# BEE_BOARD_TOP.net
KiCad netlist of a schematic drawn in Altium Designer
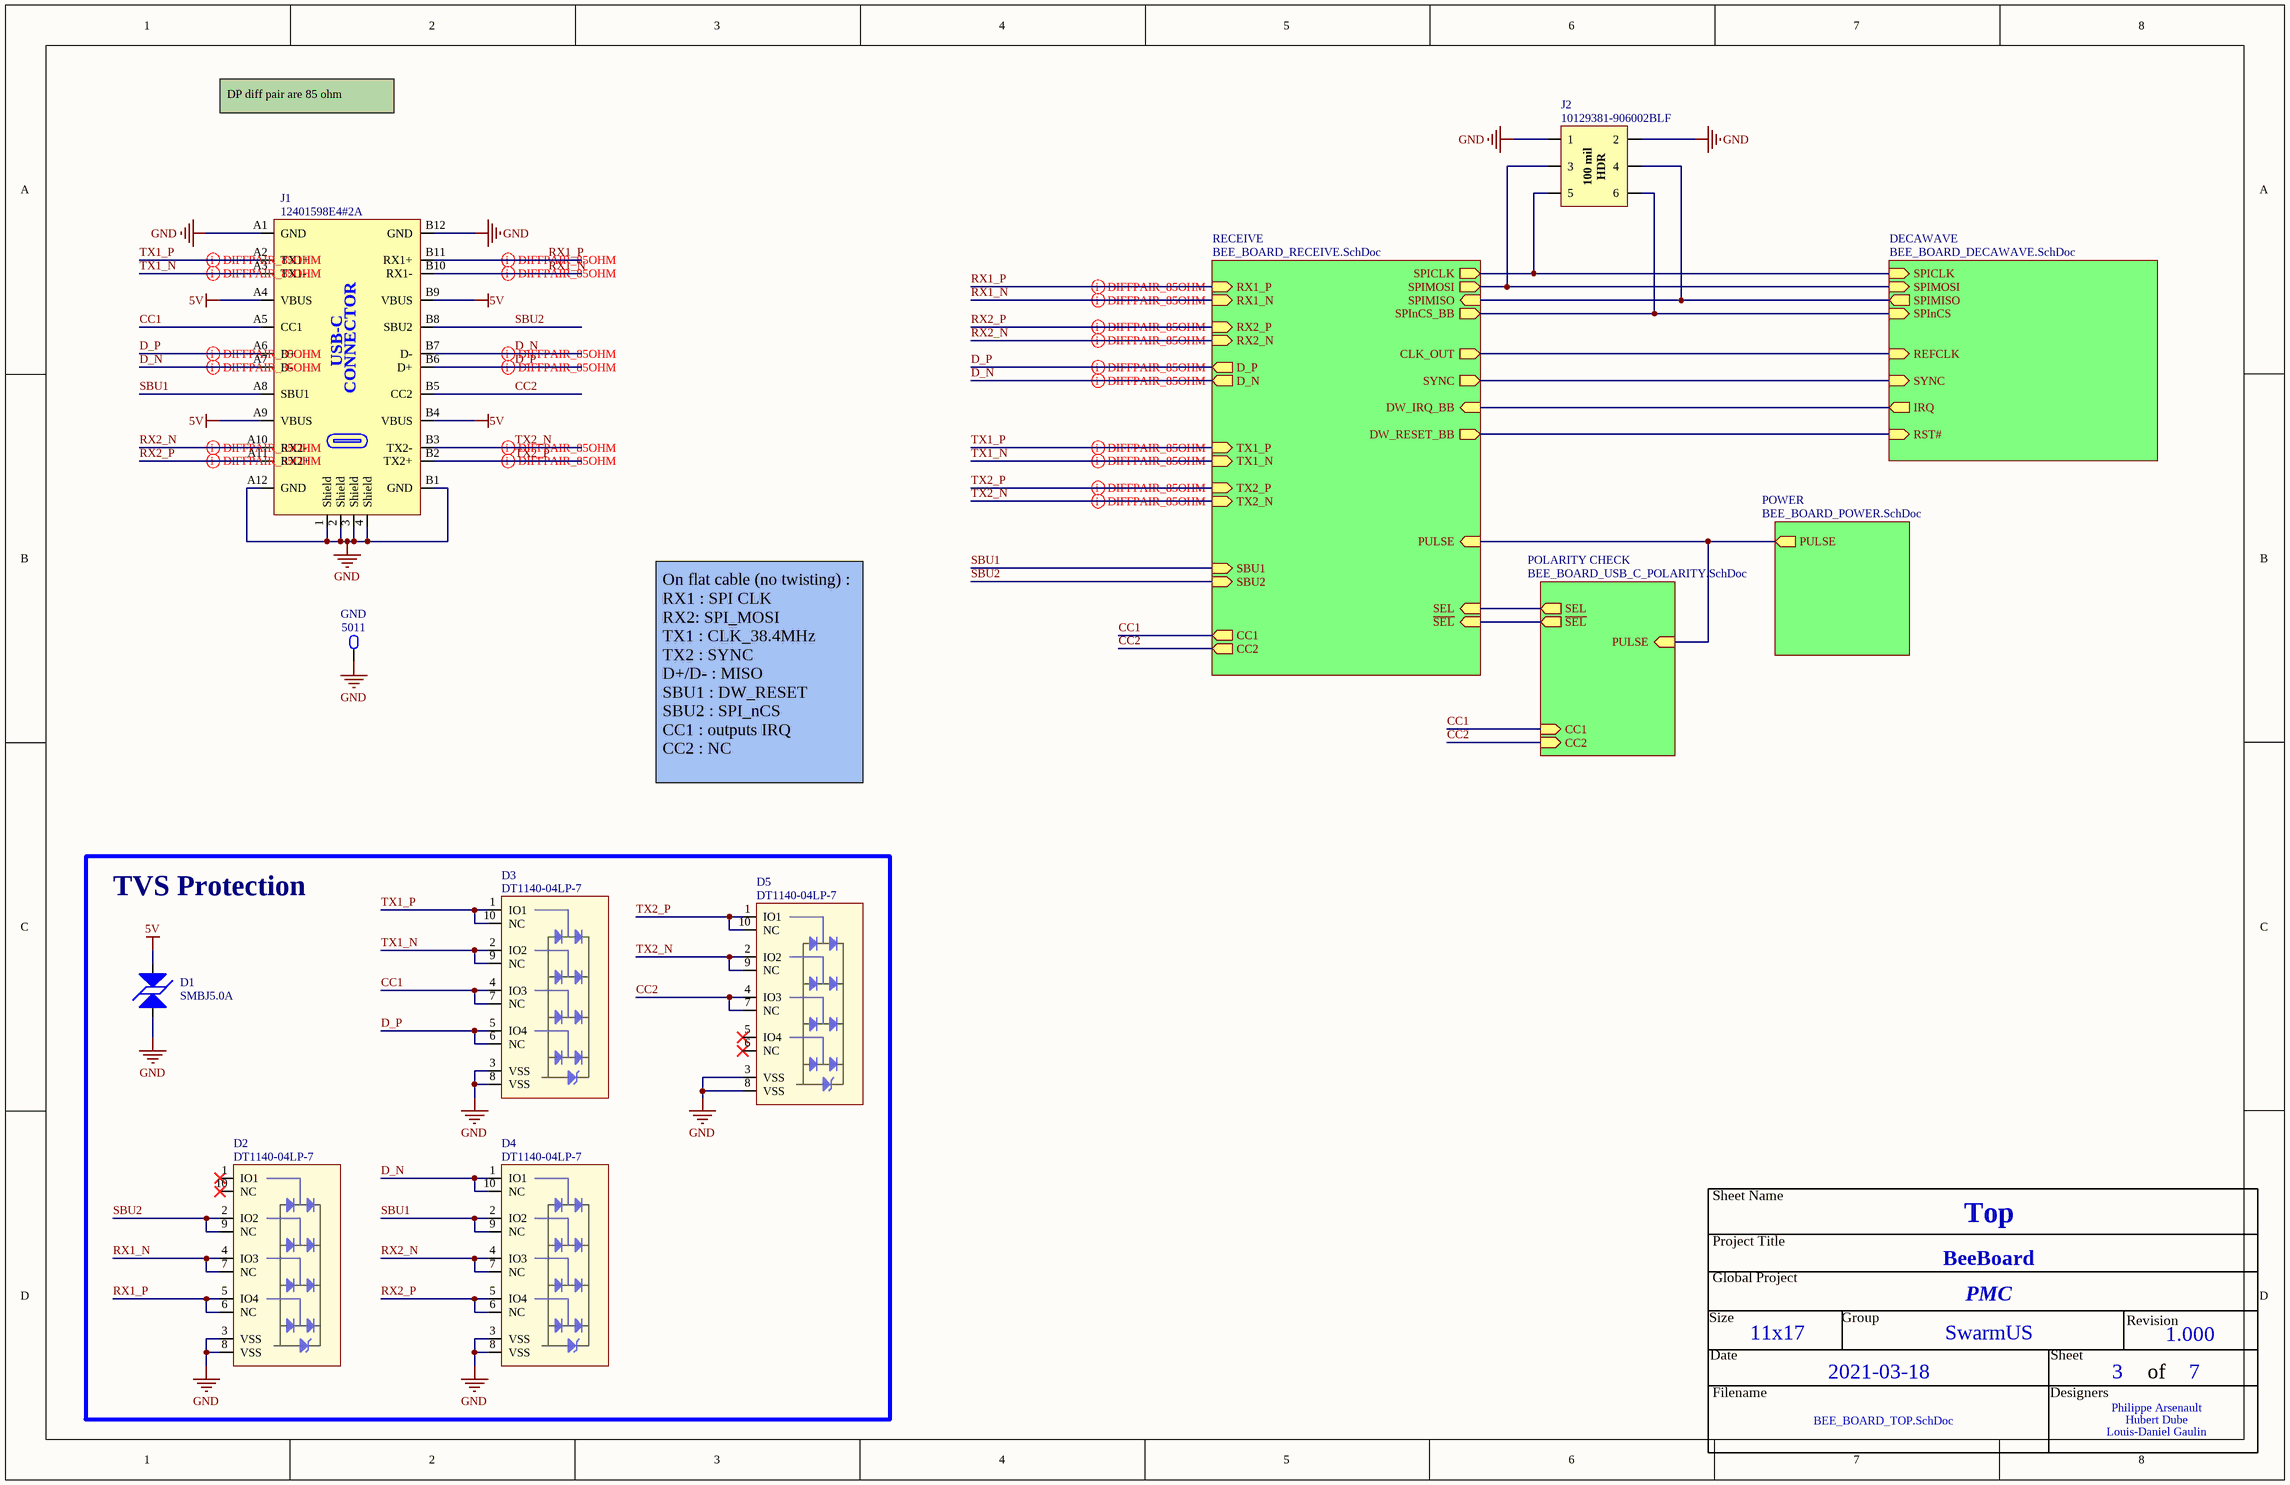
[diagram p0: BEE_BOARD_TOP.SchDoc]

(export (version "E")
  (design (tool "Eeschema 10.0.6"))
  (components
    (comp (ref "D1")
      (value "SMBJ5.0A")
      (footprint "TVS_PWR_SMBJ5.0CA")
      (description "TVS - BIDIR 5V 9.2V 600W - DO214AA")
      (fields
        (field (name "CREATEDBY/DATE") "Louis-Daniel Gaulin / 13-04-2021")
        (field (name "VERIFIEDBY") "Philippe Arsenault/2021-04-14")
      )
      (libsource (lib "SWARMUS_LIB") (part "TVS_PWR_SMBJ5.0A"))
    )
    (comp (ref "D2")
      (value "DT1140-04LP-7")
      (footprint "grams_master_lib_pcb:TVS_DATA_DT1140-04LP-7")
      (description "TVS - DIODE 5.5V 10V - 10-UFDFN")
      (fields
        (field (name "CREATEDBY/DATE") "Joël Lemay 2019-11-20")
        (field (name "VERIFIEDBY") "C.Paulin - 21/11/2019")
      )
      (libsource (lib "GRAMS_MASTER_LIB_SCH") (part "TVS_DATA_DT1140-04LP-7"))
    )
    (comp (ref "D3")
      (value "DT1140-04LP-7")
      (footprint "grams_master_lib_pcb:TVS_DATA_DT1140-04LP-7")
      (description "TVS - DIODE 5.5V 10V - 10-UFDFN")
      (fields
        (field (name "CREATEDBY/DATE") "Joël Lemay 2019-11-20")
        (field (name "VERIFIEDBY") "C.Paulin - 21/11/2019")
      )
      (libsource (lib "GRAMS_MASTER_LIB_SCH") (part "TVS_DATA_DT1140-04LP-7"))
    )
    (comp (ref "D4")
      (value "DT1140-04LP-7")
      (footprint "grams_master_lib_pcb:TVS_DATA_DT1140-04LP-7")
      (description "TVS - DIODE 5.5V 10V - 10-UFDFN")
      (fields
        (field (name "CREATEDBY/DATE") "Joël Lemay 2019-11-20")
        (field (name "VERIFIEDBY") "C.Paulin - 21/11/2019")
      )
      (libsource (lib "GRAMS_MASTER_LIB_SCH") (part "TVS_DATA_DT1140-04LP-7"))
    )
    (comp (ref "D5")
      (value "DT1140-04LP-7")
      (footprint "grams_master_lib_pcb:TVS_DATA_DT1140-04LP-7")
      (description "TVS - DIODE 5.5V 10V - 10-UFDFN")
      (fields
        (field (name "CREATEDBY/DATE") "Joël Lemay 2019-11-20")
        (field (name "VERIFIEDBY") "C.Paulin - 21/11/2019")
      )
      (libsource (lib "GRAMS_MASTER_LIB_SCH") (part "TVS_DATA_DT1140-04LP-7"))
    )
    (comp (ref "GND")
      (value "5011")
      (footprint "TPO_5011")
      (description "TPO - TEST POINT - TH")
      (fields
        (field (name "CREATEDBY/DATE") "Louis-Daniel Gauli / 02-11-2020")
        (field (name "VERIFIEDBY") "Philippe Arsenault/2020-11-06")
      )
      (libsource (lib "SWARMUS_LIB") (part "TPO_5011"))
    )
    (comp (ref "J1")
      (value "12401598E4#2A")
      (footprint "CON_USB_3.2_TypeC_12401598E4#2A")
      (description "CON_USB - USB 3.2 Gen 2 (USB 3.1 Gen 2, Superspeed + (USB 3.1)) 24 pos Receptacle - R/A")
      (fields
        (field (name "CREATEDBY/DATE") "Louis-Daniel Gaulin / 07-04-2021")
        (field (name "VERIFIEDBY") "Philippe Arsenault/2021-04-08")
      )
      (libsource (lib "SWARMUS_LIB") (part "CON_USB_3.2_TypeC_12401598E4#2A"))
    )
    (comp (ref "J2")
      (value "10129381-906002BLF")
      (footprint "CON_HDR_10129381-906002BLF")
      (description "CON - Header 6 positions 3x2  0.100\" - 6-TH")
      (fields (field (name "CREATEDBY/DATE") "Philippe Arsenault/2021-04-14"))
      (libsource (lib "SWARMUS_LIB") (part "CON_HDR_10129381-906002BLF"))
    )
  )
  (nets
    (net (code "1") (name "/CC1") (class "Default")
      (node (ref "D3") (pin "4") (pinfunction "IO3_4") (pintype "passive"))
      (node (ref "D3") (pin "7") (pinfunction "NC_7") (pintype "passive"))
      (node (ref "J1") (pin "A5") (pinfunction "CC1_A5") (pintype "passive"))
    )
    (net (code "2") (name "/CC2") (class "Default")
      (node (ref "D5") (pin "4") (pinfunction "IO3_4") (pintype "passive"))
      (node (ref "D5") (pin "7") (pinfunction "NC_7") (pintype "passive"))
      (node (ref "J1") (pin "B5") (pinfunction "CC2_B5") (pintype "passive"))
    )
    (net (code "5") (name "/D_N") (class "Default")
      (node (ref "D4") (pin "1") (pinfunction "IO1_1") (pintype "passive"))
      (node (ref "D4") (pin "10") (pinfunction "NC_10") (pintype "passive"))
      (node (ref "J1") (pin "A7") (pinfunction "D-_A7") (pintype "passive"))
      (node (ref "J1") (pin "B7") (pinfunction "D-_B7") (pintype "passive"))
    )
    (net (code "6") (name "/D_P") (class "Default")
      (node (ref "D3") (pin "5") (pinfunction "IO4_5") (pintype "passive"))
      (node (ref "D3") (pin "6") (pinfunction "NC_6") (pintype "passive"))
      (node (ref "J1") (pin "A6") (pinfunction "D+_A6") (pintype "passive"))
      (node (ref "J1") (pin "B6") (pinfunction "D+_B6") (pintype "passive"))
    )
    (net (code "9") (name "/RX1_N") (class "Default")
      (node (ref "D2") (pin "4") (pinfunction "IO3_4") (pintype "passive"))
      (node (ref "D2") (pin "7") (pinfunction "NC_7") (pintype "passive"))
      (node (ref "J1") (pin "B10") (pinfunction "RX1-_B10") (pintype "passive"))
    )
    (net (code "10") (name "/RX1_P") (class "Default")
      (node (ref "D2") (pin "5") (pinfunction "IO4_5") (pintype "passive"))
      (node (ref "D2") (pin "6") (pinfunction "NC_6") (pintype "passive"))
      (node (ref "J1") (pin "B11") (pinfunction "RX1+_B11") (pintype "passive"))
    )
    (net (code "11") (name "/RX2_N") (class "Default")
      (node (ref "D4") (pin "4") (pinfunction "IO3_4") (pintype "passive"))
      (node (ref "D4") (pin "7") (pinfunction "NC_7") (pintype "passive"))
      (node (ref "J1") (pin "A10") (pinfunction "RX2-_A10") (pintype "passive"))
    )
    (net (code "12") (name "/RX2_P") (class "Default")
      (node (ref "D4") (pin "5") (pinfunction "IO4_5") (pintype "passive"))
      (node (ref "D4") (pin "6") (pinfunction "NC_6") (pintype "passive"))
      (node (ref "J1") (pin "A11") (pinfunction "RX2+_A11") (pintype "passive"))
    )
    (net (code "13") (name "/SBU1") (class "Default")
      (node (ref "D4") (pin "2") (pinfunction "IO2_2") (pintype "passive"))
      (node (ref "D4") (pin "9") (pinfunction "NC_9") (pintype "passive"))
      (node (ref "J1") (pin "A8") (pinfunction "SBU1_A8") (pintype "passive"))
    )
    (net (code "14") (name "/SBU2") (class "Default")
      (node (ref "D2") (pin "2") (pinfunction "IO2_2") (pintype "passive"))
      (node (ref "D2") (pin "9") (pinfunction "NC_9") (pintype "passive"))
      (node (ref "J1") (pin "B8") (pinfunction "SBU2_B8") (pintype "passive"))
    )
    (net (code "17") (name "/SPICLK") (class "Default")
      (node (ref "J2") (pin "5") (pinfunction "5_5") (pintype "passive"))
    )
    (net (code "18") (name "/SPIMISO") (class "Default")
      (node (ref "J2") (pin "4") (pinfunction "4_4") (pintype "passive"))
    )
    (net (code "19") (name "/SPIMOSI") (class "Default")
      (node (ref "J2") (pin "3") (pinfunction "3_3") (pintype "passive"))
    )
    (net (code "20") (name "/SPInCS_BB") (class "Default")
      (node (ref "J2") (pin "6") (pinfunction "6_6") (pintype "passive"))
    )
    (net (code "22") (name "/TX1_N") (class "Default")
      (node (ref "D3") (pin "2") (pinfunction "IO2_2") (pintype "passive"))
      (node (ref "D3") (pin "9") (pinfunction "NC_9") (pintype "passive"))
      (node (ref "J1") (pin "A3") (pinfunction "TX1-_A3") (pintype "passive"))
    )
    (net (code "23") (name "/TX1_P") (class "Default")
      (node (ref "D3") (pin "1") (pinfunction "IO1_1") (pintype "passive"))
      (node (ref "D3") (pin "10") (pinfunction "NC_10") (pintype "passive"))
      (node (ref "J1") (pin "A2") (pinfunction "TX1+_A2") (pintype "passive"))
    )
    (net (code "24") (name "/TX2_N") (class "Default")
      (node (ref "D5") (pin "2") (pinfunction "IO2_2") (pintype "passive"))
      (node (ref "D5") (pin "9") (pinfunction "NC_9") (pintype "passive"))
      (node (ref "J1") (pin "B3") (pinfunction "TX2-_B3") (pintype "passive"))
    )
    (net (code "25") (name "/TX2_P") (class "Default")
      (node (ref "D5") (pin "1") (pinfunction "IO1_1") (pintype "passive"))
      (node (ref "D5") (pin "10") (pinfunction "NC_10") (pintype "passive"))
      (node (ref "J1") (pin "B2") (pinfunction "TX2+_B2") (pintype "passive"))
    )
    (net (code "26") (name "5V") (class "Default")
      (node (ref "D1") (pin "1") (pinfunction "1_1") (pintype "passive"))
      (node (ref "J1") (pin "A4") (pinfunction "VBUS_A4") (pintype "passive"))
      (node (ref "J1") (pin "A9") (pinfunction "VBUS_A9") (pintype "passive"))
      (node (ref "J1") (pin "B4") (pinfunction "VBUS_B4") (pintype "passive"))
      (node (ref "J1") (pin "B9") (pinfunction "VBUS_B9") (pintype "passive"))
    )
    (net (code "27") (name "GND") (class "Default")
      (node (ref "D1") (pin "2") (pinfunction "2_2") (pintype "passive"))
      (node (ref "D2") (pin "3") (pinfunction "VSS_3") (pintype "passive"))
      (node (ref "D2") (pin "8") (pinfunction "VSS_8") (pintype "passive"))
      (node (ref "D3") (pin "3") (pinfunction "VSS_3") (pintype "passive"))
      (node (ref "D3") (pin "8") (pinfunction "VSS_8") (pintype "passive"))
      (node (ref "D4") (pin "3") (pinfunction "VSS_3") (pintype "passive"))
      (node (ref "D4") (pin "8") (pinfunction "VSS_8") (pintype "passive"))
      (node (ref "D5") (pin "3") (pinfunction "VSS_3") (pintype "passive"))
      (node (ref "D5") (pin "8") (pinfunction "VSS_8") (pintype "passive"))
      (node (ref "GND") (pin "1") (pinfunction "1_1") (pintype "passive"))
      (node (ref "J1") (pin "1") (pinfunction "Shield_1") (pintype "passive"))
      (node (ref "J1") (pin "2") (pinfunction "Shield_2") (pintype "passive"))
      (node (ref "J1") (pin "3") (pinfunction "Shield_3") (pintype "passive"))
      (node (ref "J1") (pin "4") (pinfunction "Shield_4") (pintype "passive"))
      (node (ref "J1") (pin "A1") (pinfunction "GND_A1") (pintype "passive"))
      (node (ref "J1") (pin "A12") (pinfunction "GND_A12") (pintype "passive"))
      (node (ref "J1") (pin "B1") (pinfunction "GND_B1") (pintype "passive"))
      (node (ref "J1") (pin "B12") (pinfunction "GND_B12") (pintype "passive"))
      (node (ref "J2") (pin "1") (pinfunction "1_1") (pintype "passive"))
      (node (ref "J2") (pin "2") (pinfunction "2_2") (pintype "passive"))
    )
    (net (code "28") (name "unconnected-(D2-IO1-Pad1)") (class "Default")
      (node (ref "D2") (pin "1") (pinfunction "IO1_1") (pintype "passive+no_connect"))
    )
    (net (code "29") (name "unconnected-(D2-NC-Pad10)") (class "Default")
      (node (ref "D2") (pin "10") (pinfunction "NC_10") (pintype "passive+no_connect"))
    )
    (net (code "30") (name "unconnected-(D5-IO4-Pad5)") (class "Default")
      (node (ref "D5") (pin "5") (pinfunction "IO4_5") (pintype "passive+no_connect"))
    )
    (net (code "31") (name "unconnected-(D5-NC-Pad6)") (class "Default")
      (node (ref "D5") (pin "6") (pinfunction "NC_6") (pintype "passive+no_connect"))
    )
  )
)
